# ZYNQ_MIOBank_500.net
KiCad netlist of a schematic drawn in Altium Designer
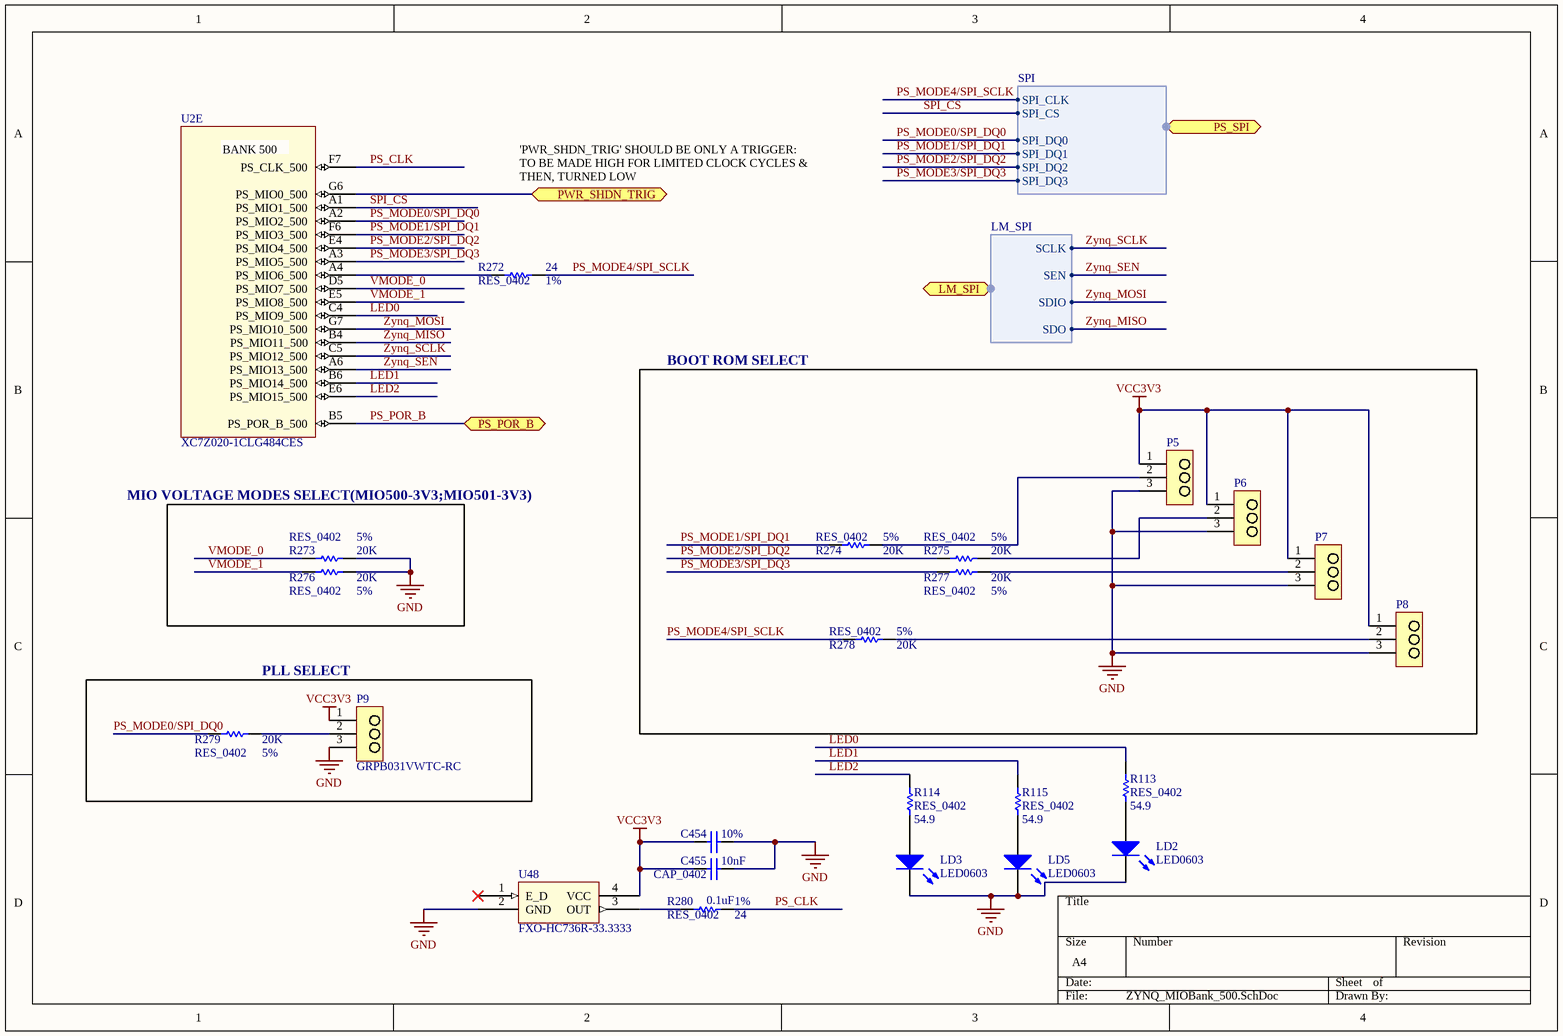
[diagram p0: ZYNQ_MIOBank_500.SchDoc]

(export (version "E")
  (design (tool "Eeschema 10.0.6"))
  (components
    (comp (ref "C454")
      (value "CAP_0402")
      (footprint "CAPC0402(1005)60_N:CAPC0402(1005)60_N")
      (description "10000pF, ceramic, 10% 6.3V X5R, 0402")
      (fields
        (field (name "ALTIUM_VALUE") "10nF")
        (field (name "TOLERANCE") "10%")
        (field (name "PART NUMBER") "GRM155R60J103KA01D")
        (field (name "MANUFACTURER") "Murata Electronics North America")
      )
      (libsource (lib "COMRAD_Database") (part "CAP_0402"))
    )
    (comp (ref "C455")
      (value "0.1uF")
      (footprint "CAPC0402(1005)60_N")
      (description "0.1uF, ceramic, 10%, 25V, X5R, 0402")
      (fields (field (name "TOLERANCE") "10%") (field (name "PART NUMBER") "TMK105BJ104KV-F"))
      (libsource (lib "COMRAD_Database") (part "CAP_0402"))
    )
    (comp (ref "LD2")
      (value "LED0603")
      (footprint "LED0603(1608)_HSMG-C190")
      (description "LED 570NM GREEN DIFF 0603 SMD")
      (fields (field (name "PART NUMBER") "\"HSMG-C190\"") (field (name "MANUFACTURER") "Avago"))
      (libsource (lib "COMRAD_Database") (part "LED0603"))
    )
    (comp (ref "LD3")
      (value "LED0603")
      (footprint "LED0603(1608)_HSMG-C190")
      (description "LED 570NM GREEN DIFF 0603 SMD")
      (fields (field (name "PART NUMBER") "\"HSMG-C190\"") (field (name "MANUFACTURER") "Avago"))
      (libsource (lib "COMRAD_Database") (part "LED0603"))
    )
    (comp (ref "LD5")
      (value "LED0603")
      (footprint "LED0603(1608)_HSMG-C190")
      (description "LED 570NM GREEN DIFF 0603 SMD")
      (fields (field (name "PART NUMBER") "\"HSMG-C190\"") (field (name "MANUFACTURER") "Avago"))
      (libsource (lib "COMRAD_Database") (part "LED0603"))
    )
    (comp (ref "P5")
      (value "GRPB031VWTC-RC")
      (footprint "Header_3-Pos_Sullins_GRPB031VWTC-RC")
      (description "CONN HEADER .050\" 3POS SMD GOLD")
      (fields (field (name "MANUFACTURER") "Sullins Connector Solutions"))
      (libsource (lib "COMRAD_Database") (part "Jumper_Header3"))
    )
    (comp (ref "P6")
      (value "GRPB031VWTC-RC")
      (footprint "Header_3-Pos_Sullins_GRPB031VWTC-RC")
      (description "CONN HEADER .050\" 3POS SMD GOLD")
      (fields (field (name "MANUFACTURER") "Sullins Connector Solutions"))
      (libsource (lib "COMRAD_Database") (part "Jumper_Header3"))
    )
    (comp (ref "P7")
      (value "GRPB031VWTC-RC")
      (footprint "Header_3-Pos_Sullins_GRPB031VWTC-RC")
      (description "CONN HEADER .050\" 3POS SMD GOLD")
      (fields (field (name "MANUFACTURER") "Sullins Connector Solutions"))
      (libsource (lib "COMRAD_Database") (part "Jumper_Header3"))
    )
    (comp (ref "P8")
      (value "GRPB031VWTC-RC")
      (footprint "Header_3-Pos_Sullins_GRPB031VWTC-RC")
      (description "CONN HEADER .050\" 3POS SMD GOLD")
      (fields (field (name "MANUFACTURER") "Sullins Connector Solutions"))
      (libsource (lib "COMRAD_Database") (part "Jumper_Header3"))
    )
    (comp (ref "P9")
      (value "GRPB031VWTC-RC")
      (footprint "Header_3-Pos_Sullins_GRPB031VWTC-RC")
      (description "CONN HEADER .050\" 3POS SMD GOLD")
      (fields (field (name "MANUFACTURER") "Sullins Connector Solutions"))
      (libsource (lib "COMRAD_Database") (part "Jumper_Header3"))
    )
    (comp (ref "R113")
      (value "RES_0402")
      (footprint "RESC0402(1005)_N")
      (description "RES 54.9 OHM 1/10W 1% 0402 SMD")
      (fields
        (field (name "ALTIUM_VALUE") "54.9")
        (field (name "PART NUMBER") "ERJ-2RKF54R9X")
        (field (name "MANUFACTURER") "Panasonic Electronic Components")
      )
      (libsource (lib "COMRAD_Database") (part "RES_0402"))
    )
    (comp (ref "R114")
      (value "RES_0402")
      (footprint "RESC0402(1005)_N")
      (description "RES 54.9 OHM 1/10W 1% 0402 SMD")
      (fields
        (field (name "ALTIUM_VALUE") "54.9")
        (field (name "PART NUMBER") "ERJ-2RKF54R9X")
        (field (name "MANUFACTURER") "Panasonic Electronic Components")
      )
      (libsource (lib "COMRAD_Database") (part "RES_0402"))
    )
    (comp (ref "R115")
      (value "RES_0402")
      (footprint "RESC0402(1005)_N")
      (description "RES 54.9 OHM 1/10W 1% 0402 SMD")
      (fields
        (field (name "ALTIUM_VALUE") "54.9")
        (field (name "PART NUMBER") "ERJ-2RKF54R9X")
        (field (name "MANUFACTURER") "Panasonic Electronic Components")
      )
      (libsource (lib "COMRAD_Database") (part "RES_0402"))
    )
    (comp (ref "R272")
      (value "RES_0402")
      (footprint "RESC0402(1005)_N")
      (description "24 ohm, 1% 1/16W, 0402")
      (fields
        (field (name "ALTIUM_VALUE") "24")
        (field (name "TOLERANCE") "1%")
        (field (name "PART NUMBER") "CRCW040224R0FKED")
        (field (name "MANUFACTURER") "Vishay/Dale")
      )
      (libsource (lib "COMRAD_Database") (part "RES_0402"))
    )
    (comp (ref "R273")
      (value "RES_0402")
      (footprint "RESC0402(1005)_N:RESC0402(1005)_N")
      (description "20K ohm, 5%, 1/16W, 0402")
      (fields
        (field (name "ALTIUM_VALUE") "20K")
        (field (name "TOLERANCE") "5%")
        (field (name "PART NUMBER") "ERJ-2GEJ203X")
        (field (name "MANUFACTURER") "Panasonic - ECG")
      )
      (libsource (lib "COMRAD_Database") (part "RES_0402"))
    )
    (comp (ref "R274")
      (value "RES_0402")
      (footprint "RESC0402(1005)_N:RESC0402(1005)_N")
      (description "20K ohm, 5%, 1/16W, 0402")
      (fields
        (field (name "ALTIUM_VALUE") "20K")
        (field (name "TOLERANCE") "5%")
        (field (name "PART NUMBER") "ERJ-2GEJ203X")
        (field (name "MANUFACTURER") "Panasonic - ECG")
      )
      (libsource (lib "COMRAD_Database") (part "RES_0402"))
    )
    (comp (ref "R275")
      (value "RES_0402")
      (footprint "RESC0402(1005)_N:RESC0402(1005)_N")
      (description "20K ohm, 5%, 1/16W, 0402")
      (fields
        (field (name "ALTIUM_VALUE") "20K")
        (field (name "TOLERANCE") "5%")
        (field (name "PART NUMBER") "ERJ-2GEJ203X")
        (field (name "MANUFACTURER") "Panasonic - ECG")
      )
      (libsource (lib "COMRAD_Database") (part "RES_0402"))
    )
    (comp (ref "R276")
      (value "RES_0402")
      (footprint "RESC0402(1005)_N:RESC0402(1005)_N")
      (description "20K ohm, 5%, 1/16W, 0402")
      (fields
        (field (name "ALTIUM_VALUE") "20K")
        (field (name "TOLERANCE") "5%")
        (field (name "PART NUMBER") "ERJ-2GEJ203X")
        (field (name "MANUFACTURER") "Panasonic - ECG")
      )
      (libsource (lib "COMRAD_Database") (part "RES_0402"))
    )
    (comp (ref "R277")
      (value "RES_0402")
      (footprint "RESC0402(1005)_N:RESC0402(1005)_N")
      (description "20K ohm, 5%, 1/16W, 0402")
      (fields
        (field (name "ALTIUM_VALUE") "20K")
        (field (name "TOLERANCE") "5%")
        (field (name "PART NUMBER") "ERJ-2GEJ203X")
        (field (name "MANUFACTURER") "Panasonic - ECG")
      )
      (libsource (lib "COMRAD_Database") (part "RES_0402"))
    )
    (comp (ref "R278")
      (value "RES_0402")
      (footprint "RESC0402(1005)_N:RESC0402(1005)_N")
      (description "20K ohm, 5%, 1/16W, 0402")
      (fields
        (field (name "ALTIUM_VALUE") "20K")
        (field (name "TOLERANCE") "5%")
        (field (name "PART NUMBER") "ERJ-2GEJ203X")
        (field (name "MANUFACTURER") "Panasonic - ECG")
      )
      (libsource (lib "COMRAD_Database") (part "RES_0402"))
    )
    (comp (ref "R279")
      (value "RES_0402")
      (footprint "RESC0402(1005)_N:RESC0402(1005)_N")
      (description "20K ohm, 5%, 1/16W, 0402")
      (fields
        (field (name "ALTIUM_VALUE") "20K")
        (field (name "TOLERANCE") "5%")
        (field (name "PART NUMBER") "ERJ-2GEJ203X")
        (field (name "MANUFACTURER") "Panasonic - ECG")
      )
      (libsource (lib "COMRAD_Database") (part "RES_0402"))
    )
    (comp (ref "R280")
      (value "RES_0402")
      (footprint "RESC0402(1005)_N")
      (description "24 ohm, 1% 1/16W, 0402")
      (fields
        (field (name "ALTIUM_VALUE") "24")
        (field (name "TOLERANCE") "1%")
        (field (name "PART NUMBER") "CRCW040224R0FKED")
        (field (name "MANUFACTURER") "Vishay/Dale")
      )
      (libsource (lib "COMRAD_Database") (part "RES_0402"))
    )
    (comp (ref "U2")
      (value "XC7Z020-1CLG484CES")
      (footprint "ZYNQ_xc7z020clg484pkg_BGA-484")
      (description "XC7Z020-1CLG484CES, Zynq-7000 All Programmable SoC")
      (fields (field (name "MANUFACTURER") "Xilinx"))
      (libsource (lib "COMRAD_Database") (part "ZYNQ_XC7Z020CLG484PKG"))
    )
    (comp (ref "U48")
      (value "FXO-HC736R-33.3333")
      (footprint "Oscillator_Fox_FXO-HC736R-33.3333_SMD")
      (description "OSC 33.3333 MHZ 3.3V HCMOS SMD")
      (fields (field (name "MANUFACTURER") "Fox Electronics"))
      (libsource (lib "COMRAD_Database") (part "Oscillator_Fox_FXO-HC736R-33.3333"))
    )
  )
  (nets
    (net (code "3") (name "/LED0") (class "Default")
      (node (ref "R113") (pin "2") (pinfunction "2_2") (pintype "passive"))
      (node (ref "U2") (pin "C4") (pinfunction "PS_MIO9_500_C4") (pintype "bidirectional"))
    )
    (net (code "4") (name "/LED1") (class "Default")
      (node (ref "R115") (pin "2") (pinfunction "2_2") (pintype "passive"))
      (node (ref "U2") (pin "B6") (pinfunction "PS_MIO14_500_B6") (pintype "bidirectional"))
    )
    (net (code "5") (name "/LED2") (class "Default")
      (node (ref "R114") (pin "2") (pinfunction "2_2") (pintype "passive"))
      (node (ref "U2") (pin "E6") (pinfunction "PS_MIO15_500_E6") (pintype "bidirectional"))
    )
    (net (code "6") (name "/PS_CLK") (class "Default")
      (node (ref "R280") (pin "2") (pinfunction "2_2") (pintype "passive"))
      (node (ref "U2") (pin "F7") (pinfunction "PS_CLK_500_F7") (pintype "bidirectional"))
    )
    (net (code "7") (name "/PS_MODE0{slash}SPI_DQ0") (class "Default")
      (node (ref "R279") (pin "1") (pinfunction "1_1") (pintype "passive"))
      (node (ref "U2") (pin "A2") (pinfunction "PS_MIO2_500_A2") (pintype "bidirectional"))
    )
    (net (code "8") (name "/PS_MODE1{slash}SPI_DQ1") (class "Default")
      (node (ref "R274") (pin "1") (pinfunction "1_1") (pintype "passive"))
      (node (ref "U2") (pin "F6") (pinfunction "PS_MIO3_500_F6") (pintype "bidirectional"))
    )
    (net (code "9") (name "/PS_MODE2{slash}SPI_DQ2") (class "Default")
      (node (ref "R275") (pin "1") (pinfunction "1_1") (pintype "passive"))
      (node (ref "U2") (pin "E4") (pinfunction "PS_MIO4_500_E4") (pintype "bidirectional"))
    )
    (net (code "10") (name "/PS_MODE3{slash}SPI_DQ3") (class "Default")
      (node (ref "R277") (pin "1") (pinfunction "1_1") (pintype "passive"))
      (node (ref "U2") (pin "A3") (pinfunction "PS_MIO5_500_A3") (pintype "bidirectional"))
    )
    (net (code "11") (name "/PS_MODE4{slash}SPI_SCLK") (class "Default")
      (node (ref "R272") (pin "2") (pinfunction "2_2") (pintype "passive"))
      (node (ref "R278") (pin "1") (pinfunction "1_1") (pintype "passive"))
    )
    (net (code "12") (name "/PS_POR_B") (class "Default")
      (node (ref "U2") (pin "B5") (pinfunction "PS_POR_B_500_B5") (pintype "bidirectional"))
    )
    (net (code "13") (name "/PWR_SHDN_TRIG") (class "Default")
      (node (ref "U2") (pin "G6") (pinfunction "PS_MIO0_500_G6") (pintype "bidirectional"))
    )
    (net (code "14") (name "/SPI_CS") (class "Default")
      (node (ref "U2") (pin "A1") (pinfunction "PS_MIO1_500_A1") (pintype "bidirectional"))
    )
    (net (code "15") (name "/VMODE_0") (class "Default")
      (node (ref "R273") (pin "1") (pinfunction "1_1") (pintype "passive"))
      (node (ref "U2") (pin "D5") (pinfunction "PS_MIO7_500_D5") (pintype "bidirectional"))
    )
    (net (code "16") (name "/VMODE_1") (class "Default")
      (node (ref "R276") (pin "1") (pinfunction "1_1") (pintype "passive"))
      (node (ref "U2") (pin "E5") (pinfunction "PS_MIO8_500_E5") (pintype "bidirectional"))
    )
    (net (code "17") (name "/Zynq_MISO") (class "Default")
      (node (ref "U2") (pin "B4") (pinfunction "PS_MIO11_500_B4") (pintype "bidirectional"))
    )
    (net (code "18") (name "/Zynq_MOSI") (class "Default")
      (node (ref "U2") (pin "G7") (pinfunction "PS_MIO10_500_G7") (pintype "bidirectional"))
    )
    (net (code "19") (name "/Zynq_SCLK") (class "Default")
      (node (ref "U2") (pin "C5") (pinfunction "PS_MIO12_500_C5") (pintype "bidirectional"))
    )
    (net (code "20") (name "/Zynq_SEN") (class "Default")
      (node (ref "U2") (pin "A6") (pinfunction "PS_MIO13_500_A6") (pintype "bidirectional"))
    )
    (net (code "23") (name "GND") (class "Default")
      (node (ref "C454") (pin "1") (pinfunction "1_1") (pintype "passive"))
      (node (ref "C455") (pin "1") (pinfunction "1_1") (pintype "passive"))
      (node (ref "LD2") (pin "1") (pinfunction "K_1") (pintype "passive"))
      (node (ref "LD3") (pin "1") (pinfunction "K_1") (pintype "passive"))
      (node (ref "LD5") (pin "1") (pinfunction "K_1") (pintype "passive"))
      (node (ref "P5") (pin "3") (pinfunction "3_3") (pintype "passive"))
      (node (ref "P6") (pin "3") (pinfunction "3_3") (pintype "passive"))
      (node (ref "P7") (pin "3") (pinfunction "3_3") (pintype "passive"))
      (node (ref "P8") (pin "3") (pinfunction "3_3") (pintype "passive"))
      (node (ref "P9") (pin "3") (pinfunction "3_3") (pintype "passive"))
      (node (ref "R273") (pin "2") (pinfunction "2_2") (pintype "passive"))
      (node (ref "R276") (pin "2") (pinfunction "2_2") (pintype "passive"))
      (node (ref "U48") (pin "2") (pinfunction "GND_2") (pintype "power_in"))
    )
    (net (code "24") (name "Net-(LD2-A)") (class "Default")
      (node (ref "LD2") (pin "2") (pinfunction "A_2") (pintype "passive"))
      (node (ref "R113") (pin "1") (pinfunction "1_1") (pintype "passive"))
    )
    (net (code "25") (name "Net-(LD3-A)") (class "Default")
      (node (ref "LD3") (pin "2") (pinfunction "A_2") (pintype "passive"))
      (node (ref "R114") (pin "1") (pinfunction "1_1") (pintype "passive"))
    )
    (net (code "26") (name "Net-(LD5-A)") (class "Default")
      (node (ref "LD5") (pin "2") (pinfunction "A_2") (pintype "passive"))
      (node (ref "R115") (pin "1") (pinfunction "1_1") (pintype "passive"))
    )
    (net (code "27") (name "Net-(P5-Pad2)") (class "Default")
      (node (ref "P5") (pin "2") (pinfunction "2_2") (pintype "passive"))
      (node (ref "R274") (pin "2") (pinfunction "2_2") (pintype "passive"))
    )
    (net (code "28") (name "Net-(P6-Pad2)") (class "Default")
      (node (ref "P6") (pin "2") (pinfunction "2_2") (pintype "passive"))
      (node (ref "R275") (pin "2") (pinfunction "2_2") (pintype "passive"))
    )
    (net (code "29") (name "Net-(P7-Pad2)") (class "Default")
      (node (ref "P7") (pin "2") (pinfunction "2_2") (pintype "passive"))
      (node (ref "R277") (pin "2") (pinfunction "2_2") (pintype "passive"))
    )
    (net (code "30") (name "Net-(P8-Pad2)") (class "Default")
      (node (ref "P8") (pin "2") (pinfunction "2_2") (pintype "passive"))
      (node (ref "R278") (pin "2") (pinfunction "2_2") (pintype "passive"))
    )
    (net (code "31") (name "Net-(P9-Pad2)") (class "Default")
      (node (ref "P9") (pin "2") (pinfunction "2_2") (pintype "passive"))
      (node (ref "R279") (pin "2") (pinfunction "2_2") (pintype "passive"))
    )
    (net (code "32") (name "Net-(U2E-PS_MIO6_500)") (class "Default")
      (node (ref "R272") (pin "1") (pinfunction "1_1") (pintype "passive"))
      (node (ref "U2") (pin "A4") (pinfunction "PS_MIO6_500_A4") (pintype "bidirectional"))
    )
    (net (code "33") (name "Net-(U48-OUT)") (class "Default")
      (node (ref "R280") (pin "1") (pinfunction "1_1") (pintype "passive"))
      (node (ref "U48") (pin "3") (pinfunction "OUT_3") (pintype "output"))
    )
    (net (code "34") (name "VCC3V3") (class "Default")
      (node (ref "C454") (pin "2") (pinfunction "2_2") (pintype "passive"))
      (node (ref "C455") (pin "2") (pinfunction "2_2") (pintype "passive"))
      (node (ref "P5") (pin "1") (pinfunction "1_1") (pintype "passive"))
      (node (ref "P6") (pin "1") (pinfunction "1_1") (pintype "passive"))
      (node (ref "P7") (pin "1") (pinfunction "1_1") (pintype "passive"))
      (node (ref "P8") (pin "1") (pinfunction "1_1") (pintype "passive"))
      (node (ref "P9") (pin "1") (pinfunction "1_1") (pintype "passive"))
      (node (ref "U48") (pin "4") (pinfunction "VCC_4") (pintype "power_in"))
    )
    (net (code "35") (name "unconnected-(U48-E_D-Pad1)") (class "Default")
      (node (ref "U48") (pin "1") (pinfunction "E_D_1") (pintype "input+no_connect"))
    )
  )
)
